# Indicateurs_DEL.net
KiCad netlist of a schematic drawn in Altium Designer
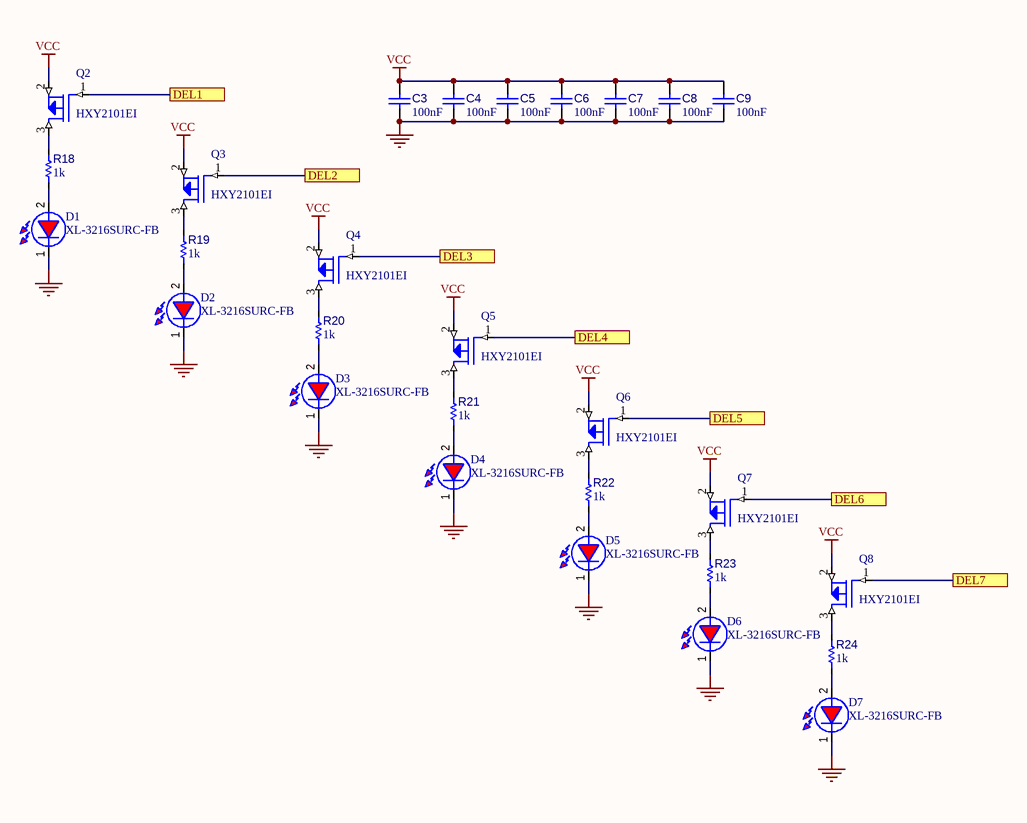
[diagram p0: Indicateurs DEL.SchDoc]

(export (version "E")
  (design (tool "Eeschema 10.0.6"))
  (components
    (comp (ref "C3")
      (value "100nF")
      (footprint "C_1608[0603]")
      (description "Capacitor type 1")
      (fields (field (name "TOLERANCE") "10%") (field (name "Comment") "CAP CER 100nF 50V 0603"))
      (libsource (lib "TEP_243-Altium_DBLib") (part "capacitor"))
    )
    (comp (ref "C4")
      (value "100nF")
      (footprint "C_1608[0603]")
      (description "Capacitor type 1")
      (fields (field (name "TOLERANCE") "10%") (field (name "Comment") "CAP CER 100nF 50V 0603"))
      (libsource (lib "TEP_243-Altium_DBLib") (part "capacitor"))
    )
    (comp (ref "C5")
      (value "100nF")
      (footprint "C_1608[0603]")
      (description "Capacitor type 1")
      (fields (field (name "TOLERANCE") "10%") (field (name "Comment") "CAP CER 100nF 50V 0603"))
      (libsource (lib "TEP_243-Altium_DBLib") (part "capacitor"))
    )
    (comp (ref "C6")
      (value "100nF")
      (footprint "C_1608[0603]")
      (description "Capacitor type 1")
      (fields (field (name "TOLERANCE") "10%") (field (name "Comment") "CAP CER 100nF 50V 0603"))
      (libsource (lib "TEP_243-Altium_DBLib") (part "capacitor"))
    )
    (comp (ref "C7")
      (value "100nF")
      (footprint "C_1608[0603]")
      (description "Capacitor type 1")
      (fields (field (name "TOLERANCE") "10%") (field (name "Comment") "CAP CER 100nF 50V 0603"))
      (libsource (lib "TEP_243-Altium_DBLib") (part "capacitor"))
    )
    (comp (ref "C8")
      (value "100nF")
      (footprint "C_1608[0603]")
      (description "Capacitor type 1")
      (fields (field (name "TOLERANCE") "10%") (field (name "Comment") "CAP CER 100nF 50V 0603"))
      (libsource (lib "TEP_243-Altium_DBLib") (part "capacitor"))
    )
    (comp (ref "C9")
      (value "100nF")
      (footprint "C_1608[0603]")
      (description "Capacitor type 1")
      (fields (field (name "TOLERANCE") "10%") (field (name "Comment") "CAP CER 100nF 50V 0603"))
      (libsource (lib "TEP_243-Altium_DBLib") (part "capacitor"))
    )
    (comp (ref "D1")
      (value "XL-3216SURC-FB")
      (footprint "LED 1206")
      (description "DEL Rouge 1206")
      (libsource (lib "TEP-AltiumLib-Discretes") (part "D_LED_RED_1206"))
    )
    (comp (ref "D2")
      (value "XL-3216SURC-FB")
      (footprint "LED 1206")
      (description "DEL Rouge 1206")
      (libsource (lib "TEP-AltiumLib-Discretes") (part "D_LED_RED_1206"))
    )
    (comp (ref "D3")
      (value "XL-3216SURC-FB")
      (footprint "LED 1206")
      (description "DEL Rouge 1206")
      (libsource (lib "TEP-AltiumLib-Discretes") (part "D_LED_RED_1206"))
    )
    (comp (ref "D4")
      (value "XL-3216SURC-FB")
      (footprint "LED 1206")
      (description "DEL Rouge 1206")
      (libsource (lib "TEP-AltiumLib-Discretes") (part "D_LED_RED_1206"))
    )
    (comp (ref "D5")
      (value "XL-3216SURC-FB")
      (footprint "LED 1206")
      (description "DEL Rouge 1206")
      (libsource (lib "TEP-AltiumLib-Discretes") (part "D_LED_RED_1206"))
    )
    (comp (ref "D6")
      (value "XL-3216SURC-FB")
      (footprint "LED 1206")
      (description "DEL Rouge 1206")
      (libsource (lib "TEP-AltiumLib-Discretes") (part "D_LED_RED_1206"))
    )
    (comp (ref "D7")
      (value "XL-3216SURC-FB")
      (footprint "LED 1206")
      (description "DEL Rouge 1206")
      (libsource (lib "TEP-AltiumLib-Discretes") (part "D_LED_RED_1206"))
    )
    (comp (ref "Q2")
      (value "HXY2101EI")
      (footprint "SOT-323")
      (description "MOSFET P-CH 20V 1.8A SOT-323")
      (libsource (lib "TEP-AltiumLib-Discretes") (part "Q_PMOS-20V-1.8A"))
    )
    (comp (ref "Q3")
      (value "HXY2101EI")
      (footprint "SOT-323")
      (description "MOSFET P-CH 20V 1.8A SOT-323")
      (libsource (lib "TEP-AltiumLib-Discretes") (part "Q_PMOS-20V-1.8A"))
    )
    (comp (ref "Q4")
      (value "HXY2101EI")
      (footprint "SOT-323")
      (description "MOSFET P-CH 20V 1.8A SOT-323")
      (libsource (lib "TEP-AltiumLib-Discretes") (part "Q_PMOS-20V-1.8A"))
    )
    (comp (ref "Q5")
      (value "HXY2101EI")
      (footprint "SOT-323")
      (description "MOSFET P-CH 20V 1.8A SOT-323")
      (libsource (lib "TEP-AltiumLib-Discretes") (part "Q_PMOS-20V-1.8A"))
    )
    (comp (ref "Q6")
      (value "HXY2101EI")
      (footprint "SOT-323")
      (description "MOSFET P-CH 20V 1.8A SOT-323")
      (libsource (lib "TEP-AltiumLib-Discretes") (part "Q_PMOS-20V-1.8A"))
    )
    (comp (ref "Q7")
      (value "HXY2101EI")
      (footprint "SOT-323")
      (description "MOSFET P-CH 20V 1.8A SOT-323")
      (libsource (lib "TEP-AltiumLib-Discretes") (part "Q_PMOS-20V-1.8A"))
    )
    (comp (ref "Q8")
      (value "HXY2101EI")
      (footprint "SOT-323")
      (description "MOSFET P-CH 20V 1.8A SOT-323")
      (libsource (lib "TEP-AltiumLib-Discretes") (part "Q_PMOS-20V-1.8A"))
    )
    (comp (ref "R18")
      (value "1k")
      (footprint "R_1608[0603]")
      (description "Resistor type 1")
      (fields (field (name "TOLERANCE") "1%") (field (name "Comment") "Res 1k 1% 0603"))
      (libsource (lib "TEP_243-Altium_DBLib") (part "resistor"))
    )
    (comp (ref "R19")
      (value "1k")
      (footprint "R_1608[0603]")
      (description "Resistor type 1")
      (fields (field (name "TOLERANCE") "1%") (field (name "Comment") "Res 1k 1% 0603"))
      (libsource (lib "TEP_243-Altium_DBLib") (part "resistor"))
    )
    (comp (ref "R20")
      (value "1k")
      (footprint "R_1608[0603]")
      (description "Resistor type 1")
      (fields (field (name "TOLERANCE") "1%") (field (name "Comment") "Res 1k 1% 0603"))
      (libsource (lib "TEP_243-Altium_DBLib") (part "resistor"))
    )
    (comp (ref "R21")
      (value "1k")
      (footprint "R_1608[0603]")
      (description "Resistor type 1")
      (fields (field (name "TOLERANCE") "1%") (field (name "Comment") "Res 1k 1% 0603"))
      (libsource (lib "TEP_243-Altium_DBLib") (part "resistor"))
    )
    (comp (ref "R22")
      (value "1k")
      (footprint "R_1608[0603]")
      (description "Resistor type 1")
      (fields (field (name "TOLERANCE") "1%") (field (name "Comment") "Res 1k 1% 0603"))
      (libsource (lib "TEP_243-Altium_DBLib") (part "resistor"))
    )
    (comp (ref "R23")
      (value "1k")
      (footprint "R_1608[0603]")
      (description "Resistor type 1")
      (fields (field (name "TOLERANCE") "1%") (field (name "Comment") "Res 1k 1% 0603"))
      (libsource (lib "TEP_243-Altium_DBLib") (part "resistor"))
    )
    (comp (ref "R24")
      (value "1k")
      (footprint "R_1608[0603]")
      (description "Resistor type 1")
      (fields (field (name "TOLERANCE") "1%") (field (name "Comment") "Res 1k 1% 0603"))
      (libsource (lib "TEP_243-Altium_DBLib") (part "resistor"))
    )
  )
  (nets
    (net (code "1") (name "/DEL1") (class "Default")
      (node (ref "Q2") (pin "1") (pinfunction "GATE_1") (pintype "input"))
    )
    (net (code "2") (name "/DEL2") (class "Default")
      (node (ref "Q3") (pin "1") (pinfunction "GATE_1") (pintype "input"))
    )
    (net (code "3") (name "/DEL3") (class "Default")
      (node (ref "Q4") (pin "1") (pinfunction "GATE_1") (pintype "input"))
    )
    (net (code "4") (name "/DEL4") (class "Default")
      (node (ref "Q5") (pin "1") (pinfunction "GATE_1") (pintype "input"))
    )
    (net (code "5") (name "/DEL5") (class "Default")
      (node (ref "Q6") (pin "1") (pinfunction "GATE_1") (pintype "input"))
    )
    (net (code "6") (name "/DEL6") (class "Default")
      (node (ref "Q7") (pin "1") (pinfunction "GATE_1") (pintype "input"))
    )
    (net (code "7") (name "/DEL7") (class "Default")
      (node (ref "Q8") (pin "1") (pinfunction "GATE_1") (pintype "input"))
    )
    (net (code "8") (name "GND") (class "Default")
      (node (ref "C3") (pin "1") (pinfunction "1_1") (pintype "passive"))
      (node (ref "C4") (pin "1") (pinfunction "1_1") (pintype "passive"))
      (node (ref "C5") (pin "1") (pinfunction "1_1") (pintype "passive"))
      (node (ref "C6") (pin "1") (pinfunction "1_1") (pintype "passive"))
      (node (ref "C7") (pin "1") (pinfunction "1_1") (pintype "passive"))
      (node (ref "C8") (pin "1") (pinfunction "1_1") (pintype "passive"))
      (node (ref "C9") (pin "1") (pinfunction "1_1") (pintype "passive"))
      (node (ref "D1") (pin "1") (pinfunction "K_1") (pintype "passive"))
      (node (ref "D2") (pin "1") (pinfunction "K_1") (pintype "passive"))
      (node (ref "D3") (pin "1") (pinfunction "K_1") (pintype "passive"))
      (node (ref "D4") (pin "1") (pinfunction "K_1") (pintype "passive"))
      (node (ref "D5") (pin "1") (pinfunction "K_1") (pintype "passive"))
      (node (ref "D6") (pin "1") (pinfunction "K_1") (pintype "passive"))
      (node (ref "D7") (pin "1") (pinfunction "K_1") (pintype "passive"))
    )
    (net (code "9") (name "Net-(D1-A)") (class "Default")
      (node (ref "D1") (pin "2") (pinfunction "A_2") (pintype "passive"))
      (node (ref "R18") (pin "1") (pinfunction "1_1") (pintype "passive"))
    )
    (net (code "10") (name "Net-(D2-A)") (class "Default")
      (node (ref "D2") (pin "2") (pinfunction "A_2") (pintype "passive"))
      (node (ref "R19") (pin "1") (pinfunction "1_1") (pintype "passive"))
    )
    (net (code "11") (name "Net-(D3-A)") (class "Default")
      (node (ref "D3") (pin "2") (pinfunction "A_2") (pintype "passive"))
      (node (ref "R20") (pin "1") (pinfunction "1_1") (pintype "passive"))
    )
    (net (code "12") (name "Net-(D4-A)") (class "Default")
      (node (ref "D4") (pin "2") (pinfunction "A_2") (pintype "passive"))
      (node (ref "R21") (pin "1") (pinfunction "1_1") (pintype "passive"))
    )
    (net (code "13") (name "Net-(D5-A)") (class "Default")
      (node (ref "D5") (pin "2") (pinfunction "A_2") (pintype "passive"))
      (node (ref "R22") (pin "1") (pinfunction "1_1") (pintype "passive"))
    )
    (net (code "14") (name "Net-(D6-A)") (class "Default")
      (node (ref "D6") (pin "2") (pinfunction "A_2") (pintype "passive"))
      (node (ref "R23") (pin "1") (pinfunction "1_1") (pintype "passive"))
    )
    (net (code "15") (name "Net-(D7-A)") (class "Default")
      (node (ref "D7") (pin "2") (pinfunction "A_2") (pintype "passive"))
      (node (ref "R24") (pin "1") (pinfunction "1_1") (pintype "passive"))
    )
    (net (code "16") (name "Net-(Q2-DRAIN)") (class "Default")
      (node (ref "Q2") (pin "3") (pinfunction "DRAIN_3") (pintype "input"))
      (node (ref "R18") (pin "2") (pinfunction "2_2") (pintype "passive"))
    )
    (net (code "17") (name "Net-(Q3-DRAIN)") (class "Default")
      (node (ref "Q3") (pin "3") (pinfunction "DRAIN_3") (pintype "input"))
      (node (ref "R19") (pin "2") (pinfunction "2_2") (pintype "passive"))
    )
    (net (code "18") (name "Net-(Q4-DRAIN)") (class "Default")
      (node (ref "Q4") (pin "3") (pinfunction "DRAIN_3") (pintype "input"))
      (node (ref "R20") (pin "2") (pinfunction "2_2") (pintype "passive"))
    )
    (net (code "19") (name "Net-(Q5-DRAIN)") (class "Default")
      (node (ref "Q5") (pin "3") (pinfunction "DRAIN_3") (pintype "input"))
      (node (ref "R21") (pin "2") (pinfunction "2_2") (pintype "passive"))
    )
    (net (code "20") (name "Net-(Q6-DRAIN)") (class "Default")
      (node (ref "Q6") (pin "3") (pinfunction "DRAIN_3") (pintype "input"))
      (node (ref "R22") (pin "2") (pinfunction "2_2") (pintype "passive"))
    )
    (net (code "21") (name "Net-(Q7-DRAIN)") (class "Default")
      (node (ref "Q7") (pin "3") (pinfunction "DRAIN_3") (pintype "input"))
      (node (ref "R23") (pin "2") (pinfunction "2_2") (pintype "passive"))
    )
    (net (code "22") (name "Net-(Q8-DRAIN)") (class "Default")
      (node (ref "Q8") (pin "3") (pinfunction "DRAIN_3") (pintype "input"))
      (node (ref "R24") (pin "2") (pinfunction "2_2") (pintype "passive"))
    )
    (net (code "23") (name "VCC") (class "Default")
      (node (ref "C3") (pin "2") (pinfunction "2_2") (pintype "passive"))
      (node (ref "C4") (pin "2") (pinfunction "2_2") (pintype "passive"))
      (node (ref "C5") (pin "2") (pinfunction "2_2") (pintype "passive"))
      (node (ref "C6") (pin "2") (pinfunction "2_2") (pintype "passive"))
      (node (ref "C7") (pin "2") (pinfunction "2_2") (pintype "passive"))
      (node (ref "C8") (pin "2") (pinfunction "2_2") (pintype "passive"))
      (node (ref "C9") (pin "2") (pinfunction "2_2") (pintype "passive"))
      (node (ref "Q2") (pin "2") (pinfunction "SOURCE_2") (pintype "input"))
      (node (ref "Q3") (pin "2") (pinfunction "SOURCE_2") (pintype "input"))
      (node (ref "Q4") (pin "2") (pinfunction "SOURCE_2") (pintype "input"))
      (node (ref "Q5") (pin "2") (pinfunction "SOURCE_2") (pintype "input"))
      (node (ref "Q6") (pin "2") (pinfunction "SOURCE_2") (pintype "input"))
      (node (ref "Q7") (pin "2") (pinfunction "SOURCE_2") (pintype "input"))
      (node (ref "Q8") (pin "2") (pinfunction "SOURCE_2") (pintype "input"))
    )
  )
)
